# DropBeacon-v1_0_0-Rev-D.net
KiCad netlist of a schematic drawn in EAGLE
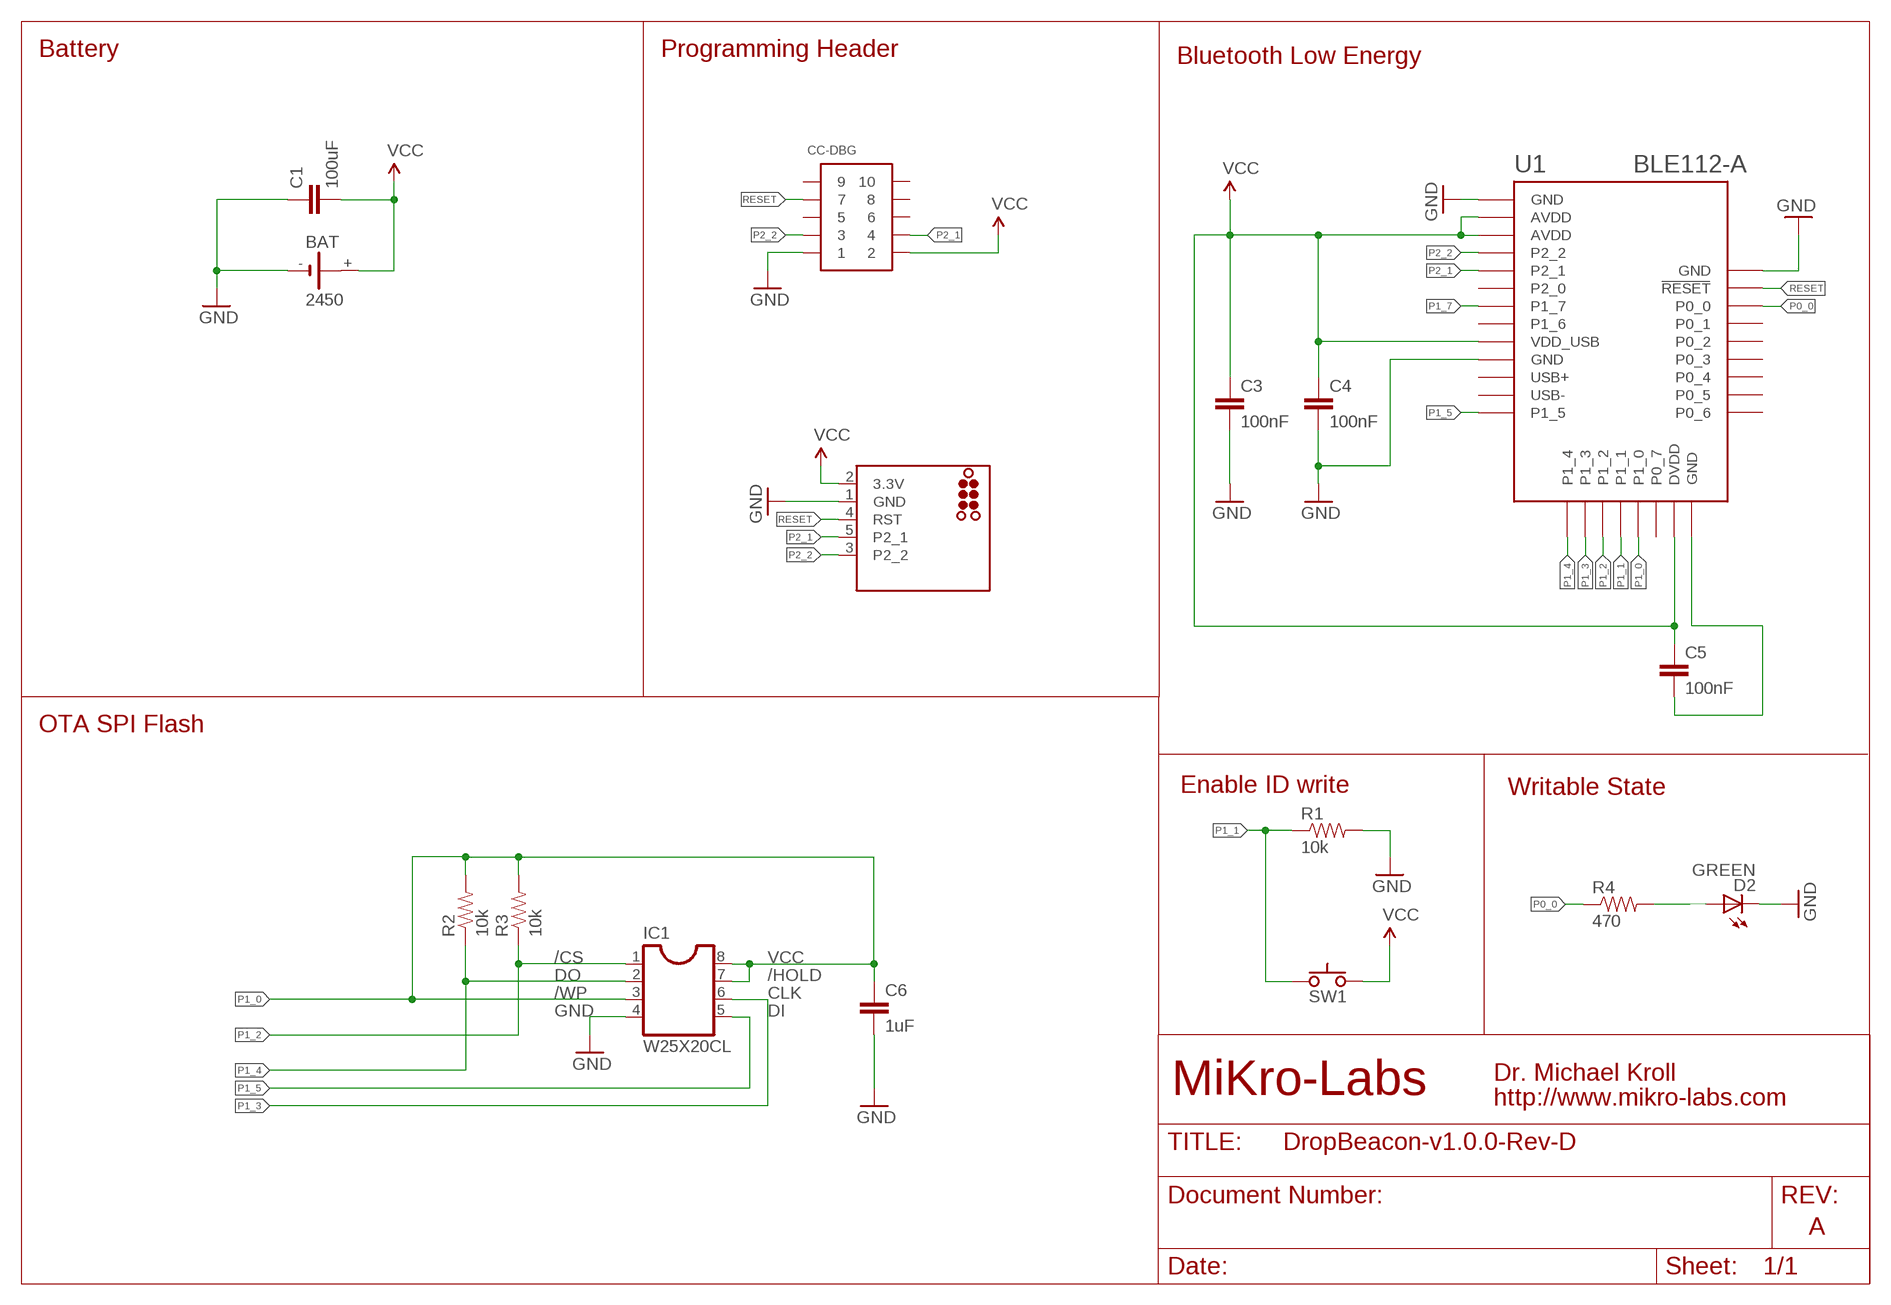
[diagram p0: schematic, sheet 1]

(export (version "E")
  (design (tool "Eeschema 10.0.6"))
  (components
    (comp (ref "BAT")
      (value "2450")
      (footprint "eagle-import:KZH24SMD")
      (libsource (lib "eagle-import") (part "2450"))
    )
    (comp (ref "C1")
      (value "100uF")
      (footprint "eagle-import:1206")
      (libsource (lib "eagle-import") (part "CAP1206"))
    )
    (comp (ref "C3")
      (value "100nF")
      (footprint "eagle-import:0603-CAP")
      (libsource (lib "eagle-import") (part "CAP0603-CAP"))
    )
    (comp (ref "C4")
      (value "100nF")
      (footprint "eagle-import:0603-CAP")
      (libsource (lib "eagle-import") (part "CAP0603-CAP"))
    )
    (comp (ref "C5")
      (value "100nF")
      (footprint "eagle-import:0603-CAP")
      (libsource (lib "eagle-import") (part "CAP0603-CAP"))
    )
    (comp (ref "C6")
      (value "1uF")
      (footprint "eagle-import:0603-CAP")
      (libsource (lib "eagle-import") (part "CAP0603-CAP"))
    )
    (comp (ref "CC-DBG")
      (value "CONN_5-2-FTSH-V")
      (footprint "eagle-import:FTSH-105-DV")
      (libsource (lib "eagle-import") (part "CONN_5-2-FTSH-V"))
    )
    (comp (ref "CC-DEBUGGER")
      (value "TC2030-CC-DEBUGGER")
      (footprint "eagle-import:TC2030-MCP-NL")
      (libsource (lib "eagle-import") (part "TC2030-CC-DEBUGGER"))
    )
    (comp (ref "D2")
      (value "GREEN")
      (footprint "eagle-import:LED-0603")
      (libsource (lib "eagle-import") (part "LED-GREEN0603"))
    )
    (comp (ref "IC1")
      (value "W25X20CL")
      (footprint "eagle-import:SO-8")
      (libsource (lib "eagle-import") (part "IC_DIL8-SOIC8"))
    )
    (comp (ref "R1")
      (value "10k")
      (footprint "eagle-import:0603-RES")
      (libsource (lib "eagle-import") (part "RESISTOR0603-RES"))
    )
    (comp (ref "R2")
      (value "10k")
      (footprint "eagle-import:0603-RES")
      (libsource (lib "eagle-import") (part "RESISTOR0603-RES"))
    )
    (comp (ref "R3")
      (value "10k")
      (footprint "eagle-import:0603-RES")
      (libsource (lib "eagle-import") (part "RESISTOR0603-RES"))
    )
    (comp (ref "R4")
      (value "470")
      (footprint "eagle-import:0603-RES")
      (libsource (lib "eagle-import") (part "RESISTOR0603-RES"))
    )
    (comp (ref "SW1")
      (value "B3U-1000P")
      (footprint "eagle-import:B3U-1000P")
      (libsource (lib "eagle-import") (part "B3U-1000P"))
    )
    (comp (ref "U1")
      (value "BLE112-A")
      (footprint "eagle-import:BLE112-A")
      (libsource (lib "eagle-import") (part "BLE112-A-VISUAL"))
    )
  )
  (nets
    (net (code "1") (name "GND") (class "Default")
      (node (ref "BAT") (pin "-") (pinfunction "-_-") (pintype "passive"))
      (node (ref "C1") (pin "1") (pinfunction "1_1") (pintype "passive"))
      (node (ref "C3") (pin "2") (pinfunction "2_2") (pintype "passive"))
      (node (ref "C4") (pin "2") (pinfunction "2_2") (pintype "passive"))
      (node (ref "C6") (pin "2") (pinfunction "2_2") (pintype "passive"))
      (node (ref "CC-DBG") (pin "1") (pinfunction "1_1") (pintype "bidirectional"))
      (node (ref "CC-DEBUGGER") (pin "1") (pinfunction "GND_1") (pintype "power_in"))
      (node (ref "D2") (pin "C") (pinfunction "C_C") (pintype "passive"))
      (node (ref "IC1") (pin "4") (pinfunction "4_4") (pintype "bidirectional"))
      (node (ref "R1") (pin "2") (pinfunction "2_2") (pintype "passive"))
      (node (ref "U1") (pin "GND") (pinfunction "GND_GND") (pintype "power_in"))
      (node (ref "U1") (pin "GND@2") (pinfunction "GND_GND@2") (pintype "power_in"))
      (node (ref "U1") (pin "GND@4") (pinfunction "GND_GND@4") (pintype "power_in"))
    )
    (net (code "2") (name "Net-(C5-Pad2)") (class "Default")
      (node (ref "C5") (pin "2") (pinfunction "2_2") (pintype "passive"))
      (node (ref "U1") (pin "GND@3") (pinfunction "GND_GND@3") (pintype "power_in"))
    )
    (net (code "3") (name "Net-(D2-PadA)") (class "Default")
      (node (ref "D2") (pin "A") (pinfunction "A_A") (pintype "passive"))
      (node (ref "R4") (pin "2") (pinfunction "2_2") (pintype "passive"))
    )
    (net (code "4") (name "P0_0") (class "Default")
      (node (ref "R4") (pin "1") (pinfunction "1_1") (pintype "passive"))
      (node (ref "U1") (pin "P0_0") (pinfunction "P0_0_P0_0") (pintype "bidirectional"))
    )
    (net (code "5") (name "P1_0") (class "Default")
      (node (ref "C6") (pin "1") (pinfunction "1_1") (pintype "passive"))
      (node (ref "IC1") (pin "3") (pinfunction "3_3") (pintype "bidirectional"))
      (node (ref "IC1") (pin "7") (pinfunction "7_7") (pintype "bidirectional"))
      (node (ref "IC1") (pin "8") (pinfunction "8_8") (pintype "bidirectional"))
      (node (ref "R2") (pin "2") (pinfunction "2_2") (pintype "passive"))
      (node (ref "R3") (pin "2") (pinfunction "2_2") (pintype "passive"))
      (node (ref "U1") (pin "P1_0") (pinfunction "P1_0_P1_0") (pintype "bidirectional"))
    )
    (net (code "6") (name "P1_1") (class "Default")
      (node (ref "R1") (pin "1") (pinfunction "1_1") (pintype "passive"))
      (node (ref "SW1") (pin "1") (pinfunction "1_1") (pintype "passive"))
      (node (ref "U1") (pin "P1_1") (pinfunction "P1_1_P1_1") (pintype "bidirectional"))
    )
    (net (code "7") (name "P1_2") (class "Default")
      (node (ref "IC1") (pin "1") (pinfunction "1_1") (pintype "bidirectional"))
      (node (ref "R3") (pin "1") (pinfunction "1_1") (pintype "passive"))
      (node (ref "U1") (pin "P1_2") (pinfunction "P1_2_P1_2") (pintype "bidirectional"))
    )
    (net (code "8") (name "P1_3") (class "Default")
      (node (ref "IC1") (pin "6") (pinfunction "6_6") (pintype "bidirectional"))
      (node (ref "U1") (pin "P1_3") (pinfunction "P1_3_P1_3") (pintype "bidirectional"))
    )
    (net (code "9") (name "P1_4") (class "Default")
      (node (ref "IC1") (pin "2") (pinfunction "2_2") (pintype "bidirectional"))
      (node (ref "R2") (pin "1") (pinfunction "1_1") (pintype "passive"))
      (node (ref "U1") (pin "P1_4") (pinfunction "P1_4_P1_4") (pintype "bidirectional"))
    )
    (net (code "10") (name "P1_5") (class "Default")
      (node (ref "IC1") (pin "5") (pinfunction "5_5") (pintype "bidirectional"))
      (node (ref "U1") (pin "P1_5") (pinfunction "P1_5_P1_5") (pintype "bidirectional"))
    )
    (net (code "11") (name "P1_7") (class "Default")
      (node (ref "U1") (pin "P1_7") (pinfunction "P1_7_P1_7") (pintype "bidirectional"))
    )
    (net (code "12") (name "P2_1") (class "Default")
      (node (ref "CC-DBG") (pin "4") (pinfunction "4_4") (pintype "bidirectional"))
      (node (ref "CC-DEBUGGER") (pin "5") (pinfunction "P2_1_5") (pintype "bidirectional"))
      (node (ref "U1") (pin "P2_1") (pinfunction "P2_1_P2_1") (pintype "bidirectional"))
    )
    (net (code "13") (name "P2_2") (class "Default")
      (node (ref "CC-DBG") (pin "3") (pinfunction "3_3") (pintype "bidirectional"))
      (node (ref "CC-DEBUGGER") (pin "3") (pinfunction "P2_2_3") (pintype "bidirectional"))
      (node (ref "U1") (pin "P2_2") (pinfunction "P2_2_P2_2") (pintype "bidirectional"))
    )
    (net (code "14") (name "RESET") (class "Default")
      (node (ref "CC-DBG") (pin "7") (pinfunction "7_7") (pintype "bidirectional"))
      (node (ref "CC-DEBUGGER") (pin "4") (pinfunction "RST_4") (pintype "bidirectional"))
      (node (ref "U1") (pin "RESET") (pinfunction "RESET_RESET") (pintype "input"))
    )
    (net (code "15") (name "VCC") (class "Default")
      (node (ref "BAT") (pin "+") (pinfunction "+_+") (pintype "passive"))
      (node (ref "C1") (pin "2") (pinfunction "2_2") (pintype "passive"))
      (node (ref "C3") (pin "1") (pinfunction "1_1") (pintype "passive"))
      (node (ref "C4") (pin "1") (pinfunction "1_1") (pintype "passive"))
      (node (ref "C5") (pin "1") (pinfunction "1_1") (pintype "passive"))
      (node (ref "CC-DBG") (pin "2") (pinfunction "2_2") (pintype "bidirectional"))
      (node (ref "CC-DEBUGGER") (pin "2") (pinfunction "3.3V_2") (pintype "power_in"))
      (node (ref "SW1") (pin "2") (pinfunction "2_2") (pintype "passive"))
      (node (ref "U1") (pin "AVDD") (pinfunction "AVDD_AVDD") (pintype "power_in"))
      (node (ref "U1") (pin "AVDD@2") (pinfunction "AVDD_AVDD@2") (pintype "power_in"))
      (node (ref "U1") (pin "DVDD") (pinfunction "DVDD_DVDD") (pintype "power_in"))
      (node (ref "U1") (pin "VDD_USB") (pinfunction "VDD_USB_VDD_USB") (pintype "power_in"))
    )
    (net (code "16") (name "unconnected-(CC-DBG-Pad5)") (class "Default")
      (node (ref "CC-DBG") (pin "5") (pinfunction "5_5") (pintype "bidirectional"))
    )
    (net (code "17") (name "unconnected-(CC-DBG-Pad6)") (class "Default")
      (node (ref "CC-DBG") (pin "6") (pinfunction "6_6") (pintype "bidirectional"))
    )
    (net (code "18") (name "unconnected-(CC-DBG-Pad8)") (class "Default")
      (node (ref "CC-DBG") (pin "8") (pinfunction "8_8") (pintype "bidirectional"))
    )
    (net (code "19") (name "unconnected-(CC-DBG-Pad9)") (class "Default")
      (node (ref "CC-DBG") (pin "9") (pinfunction "9_9") (pintype "bidirectional"))
    )
    (net (code "20") (name "unconnected-(CC-DBG-Pad10)") (class "Default")
      (node (ref "CC-DBG") (pin "10") (pinfunction "10_10") (pintype "bidirectional"))
    )
    (net (code "21") (name "unconnected-(U1-PadP0_1)") (class "Default")
      (node (ref "U1") (pin "P0_1") (pinfunction "P0_1_P0_1") (pintype "bidirectional"))
    )
    (net (code "22") (name "unconnected-(U1-PadP0_2)") (class "Default")
      (node (ref "U1") (pin "P0_2") (pinfunction "P0_2_P0_2") (pintype "bidirectional"))
    )
    (net (code "23") (name "unconnected-(U1-PadP0_3)") (class "Default")
      (node (ref "U1") (pin "P0_3") (pinfunction "P0_3_P0_3") (pintype "bidirectional"))
    )
    (net (code "24") (name "unconnected-(U1-PadP0_4)") (class "Default")
      (node (ref "U1") (pin "P0_4") (pinfunction "P0_4_P0_4") (pintype "bidirectional"))
    )
    (net (code "25") (name "unconnected-(U1-PadP0_5)") (class "Default")
      (node (ref "U1") (pin "P0_5") (pinfunction "P0_5_P0_5") (pintype "bidirectional"))
    )
    (net (code "26") (name "unconnected-(U1-PadP0_6)") (class "Default")
      (node (ref "U1") (pin "P0_6") (pinfunction "P0_6_P0_6") (pintype "bidirectional"))
    )
    (net (code "27") (name "unconnected-(U1-PadP0_7)") (class "Default")
      (node (ref "U1") (pin "P0_7") (pinfunction "P0_7_P0_7") (pintype "bidirectional"))
    )
    (net (code "28") (name "unconnected-(U1-PadP1_6)") (class "Default")
      (node (ref "U1") (pin "P1_6") (pinfunction "P1_6_P1_6") (pintype "bidirectional"))
    )
    (net (code "29") (name "unconnected-(U1-PadP2_0)") (class "Default")
      (node (ref "U1") (pin "P2_0") (pinfunction "P2_0_P2_0") (pintype "bidirectional"))
    )
    (net (code "30") (name "unconnected-(U1-PadUSB+)") (class "Default")
      (node (ref "U1") (pin "USB+") (pinfunction "USB+_USB+") (pintype "bidirectional"))
    )
    (net (code "31") (name "unconnected-(U1-PadUSB-)") (class "Default")
      (node (ref "U1") (pin "USB-") (pinfunction "USB-_USB-") (pintype "bidirectional"))
    )
  )
)
